# Grove_-_Differential_Amplifier_v1_1.net
KiCad netlist of a schematic drawn in EAGLE
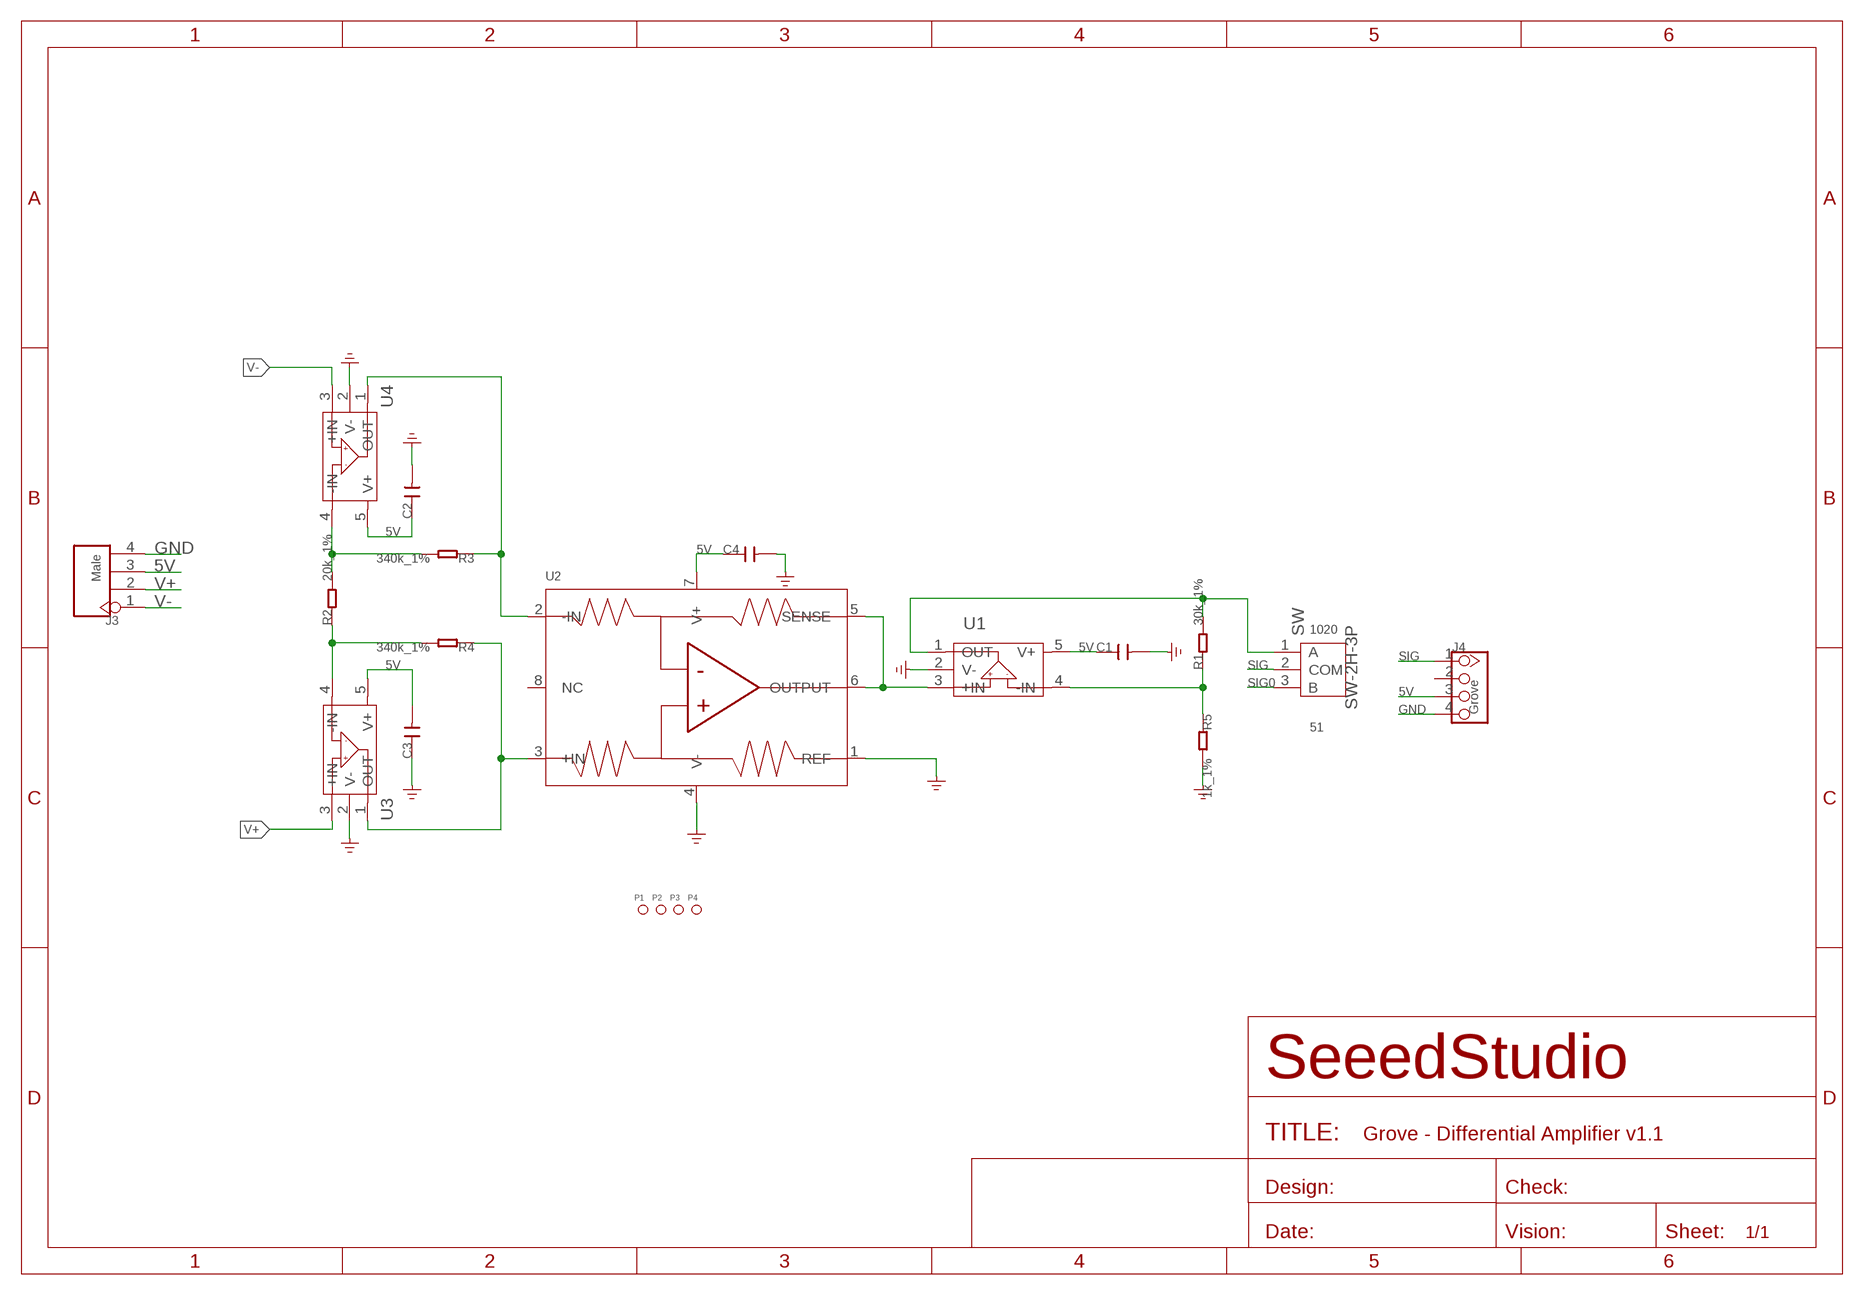
[diagram p0: schematic, sheet 1]

(export (version "E")
  (design (tool "Eeschema 10.0.6"))
  (components
    (comp (ref "C1")
      (value "C-0603")
      (footprint "eagle-import:C0603")
      (libsource (lib "eagle-import") (part "C-0603"))
    )
    (comp (ref "C2")
      (value "C-0603")
      (footprint "eagle-import:C0603")
      (libsource (lib "eagle-import") (part "C-0603"))
    )
    (comp (ref "C3")
      (value "C-0603")
      (footprint "eagle-import:C0603")
      (libsource (lib "eagle-import") (part "C-0603"))
    )
    (comp (ref "C4")
      (value "C-0603")
      (footprint "eagle-import:C0603")
      (libsource (lib "eagle-import") (part "C-0603"))
    )
    (comp (ref "J3")
      (value "Male")
      (footprint "eagle-import:4P-65_35MIL")
      (libsource (lib "eagle-import") (part "HEADER-4P-60/35MIL"))
    )
    (comp (ref "J4")
      (value "Grove")
      (footprint "eagle-import:4P-2.0")
      (libsource (lib "eagle-import") (part "TWIG-4P-2.0-2.0"))
    )
    (comp (ref "P1")
      (value "PAD-MARK")
      (footprint "eagle-import:ROUND-MARK-1.0")
      (fields (field (name "PARTNO") "DNP"))
      (libsource (lib "eagle-import") (part "PAD-MARK"))
    )
    (comp (ref "P2")
      (value "PAD-MARK")
      (footprint "eagle-import:ROUND-MARK-1.0")
      (fields (field (name "PARTNO") "DNP"))
      (libsource (lib "eagle-import") (part "PAD-MARK"))
    )
    (comp (ref "P3")
      (value "PAD-MARK")
      (footprint "eagle-import:ROUND-MARK-1.0")
      (fields (field (name "PARTNO") "DNP"))
      (libsource (lib "eagle-import") (part "PAD-MARK"))
    )
    (comp (ref "P4")
      (value "PAD-MARK")
      (footprint "eagle-import:ROUND-MARK-1.0")
      (fields (field (name "PARTNO") "DNP"))
      (libsource (lib "eagle-import") (part "PAD-MARK"))
    )
    (comp (ref "R1")
      (value "30k_1%")
      (footprint "eagle-import:R0603")
      (libsource (lib "eagle-import") (part "R-0603"))
    )
    (comp (ref "R2")
      (value "20k_1%")
      (footprint "eagle-import:R0603")
      (libsource (lib "eagle-import") (part "R-0603"))
    )
    (comp (ref "R3")
      (value "340k_1%")
      (footprint "eagle-import:R0603")
      (libsource (lib "eagle-import") (part "R-0603"))
    )
    (comp (ref "R4")
      (value "340k_1%")
      (footprint "eagle-import:R0603")
      (libsource (lib "eagle-import") (part "R-0603"))
    )
    (comp (ref "R5")
      (value "1k_1%")
      (footprint "eagle-import:R0603")
      (libsource (lib "eagle-import") (part "R-0603"))
    )
    (comp (ref "SW")
      (value "SW-2H-3P")
      (footprint "eagle-import:3P-2CH-3.54X8.5")
      (libsource (lib "eagle-import") (part "SWITCH-2H-3P'--'"))
    )
    (comp (ref "U1")
      (value "OPA333DBV")
      (footprint "eagle-import:SOT23-5")
      (libsource (lib "eagle-import") (part "OPA333DBV"))
    )
    (comp (ref "U2")
      (value "INA132U/2K5")
      (footprint "eagle-import:SOIC8-6.0")
      (libsource (lib "eagle-import") (part "INA132U/2K5"))
    )
    (comp (ref "U3")
      (value "OPA333DBV")
      (footprint "eagle-import:SOT23-5")
      (libsource (lib "eagle-import") (part "OPA333DBV"))
    )
    (comp (ref "U4")
      (value "OPA333DBV")
      (footprint "eagle-import:SOT23-5")
      (libsource (lib "eagle-import") (part "OPA333DBV"))
    )
  )
  (nets
    (net (code "1") (name "/5V") (class "Default")
      (node (ref "C1") (pin "1") (pinfunction "1_1") (pintype "passive"))
      (node (ref "C2") (pin "1") (pinfunction "1_1") (pintype "passive"))
      (node (ref "C3") (pin "2") (pinfunction "2_2") (pintype "passive"))
      (node (ref "C4") (pin "1") (pinfunction "1_1") (pintype "passive"))
      (node (ref "J3") (pin "3") (pinfunction "P$3_3") (pintype "bidirectional"))
      (node (ref "J4") (pin "3") (pinfunction "3_3") (pintype "bidirectional"))
      (node (ref "U1") (pin "5") (pinfunction "V+_5") (pintype "bidirectional"))
      (node (ref "U2") (pin "7") (pinfunction "V+_7") (pintype "bidirectional"))
      (node (ref "U3") (pin "5") (pinfunction "V+_5") (pintype "bidirectional"))
      (node (ref "U4") (pin "5") (pinfunction "V+_5") (pintype "bidirectional"))
    )
    (net (code "2") (name "/SIG") (class "Default")
      (node (ref "J4") (pin "1") (pinfunction "1_1") (pintype "bidirectional"))
      (node (ref "SW") (pin "2") (pinfunction "COM_2") (pintype "bidirectional"))
    )
    (net (code "3") (name "/SIG0") (class "Default")
      (node (ref "SW") (pin "3") (pinfunction "B_3") (pintype "bidirectional"))
      (node (ref "U1") (pin "3") (pinfunction "+IN_3") (pintype "bidirectional"))
      (node (ref "U2") (pin "5") (pinfunction "SENSE_5") (pintype "bidirectional"))
      (node (ref "U2") (pin "6") (pinfunction "OUTPUT_6") (pintype "bidirectional"))
    )
    (net (code "4") (name "GND_POWER") (class "Default")
      (node (ref "C1") (pin "2") (pinfunction "2_2") (pintype "passive"))
      (node (ref "C2") (pin "2") (pinfunction "2_2") (pintype "passive"))
      (node (ref "C3") (pin "1") (pinfunction "1_1") (pintype "passive"))
      (node (ref "C4") (pin "2") (pinfunction "2_2") (pintype "passive"))
      (node (ref "J3") (pin "4") (pinfunction "P$4_4") (pintype "bidirectional"))
      (node (ref "J4") (pin "4") (pinfunction "4_4") (pintype "bidirectional"))
      (node (ref "R5") (pin "2") (pinfunction "2_2") (pintype "passive"))
      (node (ref "U1") (pin "2") (pinfunction "V-_2") (pintype "bidirectional"))
      (node (ref "U2") (pin "1") (pinfunction "REF_1") (pintype "bidirectional"))
      (node (ref "U2") (pin "4") (pinfunction "V-_4") (pintype "bidirectional"))
      (node (ref "U3") (pin "2") (pinfunction "V-_2") (pintype "bidirectional"))
      (node (ref "U4") (pin "2") (pinfunction "V-_2") (pintype "bidirectional"))
    )
    (net (code "5") (name "Net-(SW-A)") (class "Default")
      (node (ref "R1") (pin "2") (pinfunction "2_2") (pintype "passive"))
      (node (ref "SW") (pin "1") (pinfunction "A_1") (pintype "bidirectional"))
      (node (ref "U1") (pin "1") (pinfunction "OUT_1") (pintype "bidirectional"))
    )
    (net (code "6") (name "Net-(U1--IN)") (class "Default")
      (node (ref "R1") (pin "1") (pinfunction "1_1") (pintype "passive"))
      (node (ref "R5") (pin "1") (pinfunction "1_1") (pintype "passive"))
      (node (ref "U1") (pin "4") (pinfunction "-IN_4") (pintype "bidirectional"))
    )
    (net (code "7") (name "Net-(U2-+IN)") (class "Default")
      (node (ref "R4") (pin "1") (pinfunction "1_1") (pintype "passive"))
      (node (ref "U2") (pin "3") (pinfunction "+IN_3") (pintype "bidirectional"))
      (node (ref "U3") (pin "1") (pinfunction "OUT_1") (pintype "bidirectional"))
    )
    (net (code "8") (name "Net-(U2--IN)") (class "Default")
      (node (ref "R3") (pin "1") (pinfunction "1_1") (pintype "passive"))
      (node (ref "U2") (pin "2") (pinfunction "-IN_2") (pintype "bidirectional"))
      (node (ref "U4") (pin "1") (pinfunction "OUT_1") (pintype "bidirectional"))
    )
    (net (code "9") (name "Net-(U3--IN)") (class "Default")
      (node (ref "R2") (pin "1") (pinfunction "1_1") (pintype "passive"))
      (node (ref "R4") (pin "2") (pinfunction "2_2") (pintype "passive"))
      (node (ref "U3") (pin "4") (pinfunction "-IN_4") (pintype "bidirectional"))
    )
    (net (code "10") (name "Net-(U4--IN)") (class "Default")
      (node (ref "R2") (pin "2") (pinfunction "2_2") (pintype "passive"))
      (node (ref "R3") (pin "2") (pinfunction "2_2") (pintype "passive"))
      (node (ref "U4") (pin "4") (pinfunction "-IN_4") (pintype "bidirectional"))
    )
    (net (code "11") (name "V+") (class "Default")
      (node (ref "J3") (pin "2") (pinfunction "P$2_2") (pintype "bidirectional"))
      (node (ref "U3") (pin "3") (pinfunction "+IN_3") (pintype "bidirectional"))
    )
    (net (code "12") (name "V-") (class "Default")
      (node (ref "J3") (pin "1") (pinfunction "P$1_1") (pintype "bidirectional"))
      (node (ref "U4") (pin "3") (pinfunction "+IN_3") (pintype "bidirectional"))
    )
    (net (code "13") (name "unconnected-(J4-Pad2)") (class "Default")
      (node (ref "J4") (pin "2") (pinfunction "2_2") (pintype "bidirectional"))
    )
    (net (code "14") (name "unconnected-(U2-NC-Pad8)") (class "Default")
      (node (ref "U2") (pin "8") (pinfunction "NC_8") (pintype "bidirectional"))
    )
  )
)
